# ttl.net
KiCad netlist of a schematic drawn in EAGLE
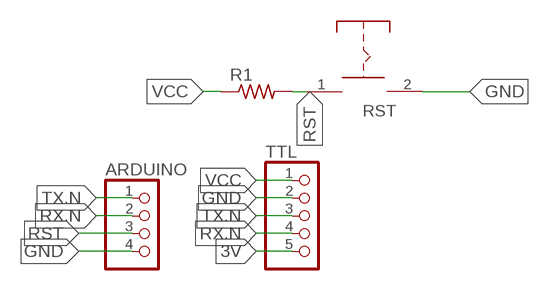
[diagram p0: schematic, sheet 1]

(export (version "E")
  (design (tool "Eeschema 10.0.6"))
  (components
    (comp (ref "ARDUINO")
      (value "PINHD-1X4")
      (footprint "eagle-import:1X04")
      (libsource (lib "eagle-import") (part "PINHD-1X4"))
    )
    (comp (ref "R1")
      (value "R-US_0204/5")
      (footprint "eagle-import:0204_5")
      (libsource (lib "eagle-import") (part "R-US_0204/5"))
    )
    (comp (ref "RST")
      (value "PUSHBOTTON")
      (footprint "eagle-import:PUSHBOTTON")
      (libsource (lib "eagle-import") (part "PUSHBOTTON"))
    )
    (comp (ref "TTL")
      (value "PINHD-1X5")
      (footprint "eagle-import:1X05")
      (libsource (lib "eagle-import") (part "PINHD-1X5"))
    )
  )
  (nets
    (net (code "1") (name "3V") (class "Default")
      (node (ref "TTL") (pin "5") (pinfunction "5_5") (pintype "passive"))
    )
    (net (code "2") (name "GND") (class "Default")
      (node (ref "ARDUINO") (pin "4") (pinfunction "4_4") (pintype "passive"))
      (node (ref "RST") (pin "2") (pinfunction "2_2") (pintype "bidirectional"))
      (node (ref "TTL") (pin "2") (pinfunction "2_2") (pintype "passive"))
    )
    (net (code "3") (name "RST") (class "Default")
      (node (ref "ARDUINO") (pin "3") (pinfunction "3_3") (pintype "passive"))
      (node (ref "R1") (pin "2") (pinfunction "2_2") (pintype "passive"))
      (node (ref "RST") (pin "1") (pinfunction "1_1") (pintype "bidirectional"))
    )
    (net (code "4") (name "RX.N") (class "Default")
      (node (ref "ARDUINO") (pin "2") (pinfunction "2_2") (pintype "passive"))
      (node (ref "TTL") (pin "4") (pinfunction "4_4") (pintype "passive"))
    )
    (net (code "5") (name "TX.N") (class "Default")
      (node (ref "ARDUINO") (pin "1") (pinfunction "1_1") (pintype "passive"))
      (node (ref "TTL") (pin "3") (pinfunction "3_3") (pintype "passive"))
    )
    (net (code "6") (name "VCC") (class "Default")
      (node (ref "R1") (pin "1") (pinfunction "1_1") (pintype "passive"))
      (node (ref "TTL") (pin "1") (pinfunction "1_1") (pintype "passive"))
    )
  )
)
